# board.net
KiCad netlist of a schematic drawn in EAGLE
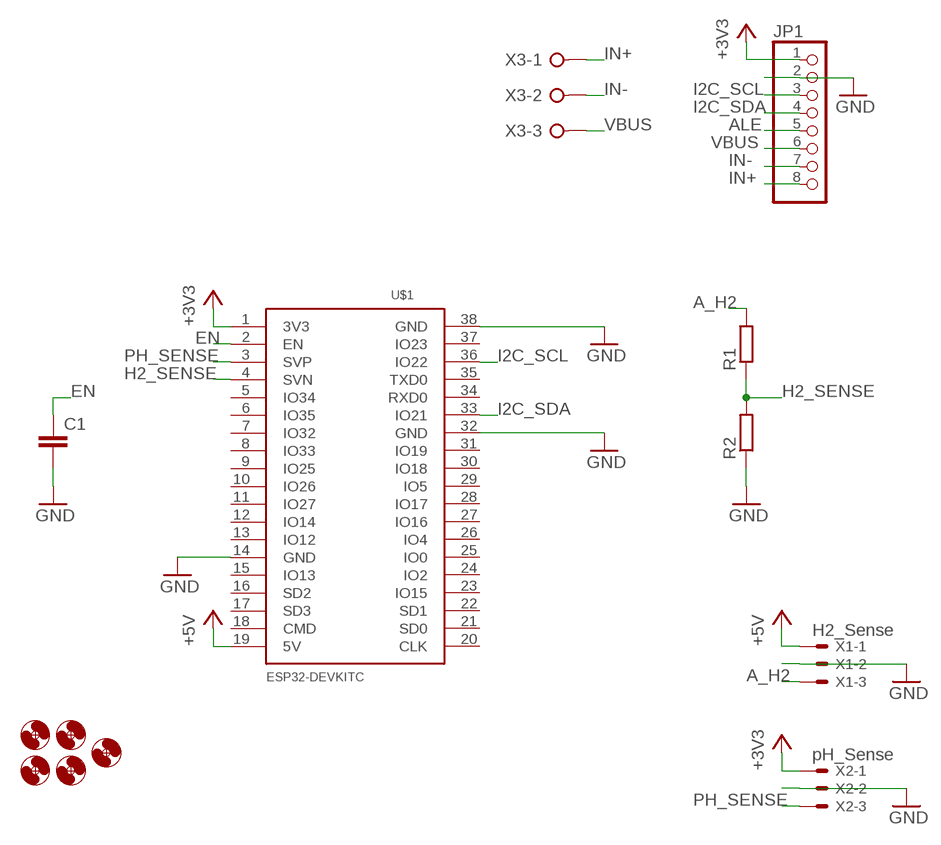
[diagram p0: schematic, sheet 1]

(export (version "E")
  (design (tool "Eeschema 10.0.6"))
  (components
    (comp (ref "C1")
      (value "C-EUC0805")
      (footprint "eagle-import:C0805")
      (libsource (lib "eagle-import") (part "C-EUC0805"))
    )
    (comp (ref "H1")
      (value "MOUNT-HOLE3.0")
      (footprint "eagle-import:3,0")
      (libsource (lib "eagle-import") (part "MOUNT-HOLE3.0"))
    )
    (comp (ref "H2")
      (value "MOUNT-HOLE3.0")
      (footprint "eagle-import:3,0")
      (libsource (lib "eagle-import") (part "MOUNT-HOLE3.0"))
    )
    (comp (ref "H3")
      (value "MOUNT-HOLE3.0")
      (footprint "eagle-import:3,0")
      (libsource (lib "eagle-import") (part "MOUNT-HOLE3.0"))
    )
    (comp (ref "H4")
      (value "MOUNT-HOLE3.0")
      (footprint "eagle-import:3,0")
      (libsource (lib "eagle-import") (part "MOUNT-HOLE3.0"))
    )
    (comp (ref "H6")
      (value "MOUNT-HOLE3.0")
      (footprint "eagle-import:3,0")
      (libsource (lib "eagle-import") (part "MOUNT-HOLE3.0"))
    )
    (comp (ref "JP1")
      (value "PINHD-1X8")
      (footprint "eagle-import:1X08")
      (libsource (lib "eagle-import") (part "PINHD-1X8"))
    )
    (comp (ref "R1")
      (value "R-EU_R0805")
      (footprint "eagle-import:R0805")
      (libsource (lib "eagle-import") (part "R-EU_R0805"))
    )
    (comp (ref "R2")
      (value "R-EU_R0805")
      (footprint "eagle-import:R0805")
      (libsource (lib "eagle-import") (part "R-EU_R0805"))
    )
    (comp (ref "U$1")
      (value "ESP32DEVKITC")
      (footprint "eagle-import:ESP32-DEVKITC")
      (libsource (lib "eagle-import") (part "ESP32DEVKITC"))
    )
    (comp (ref "X1")
      (value "H2_Sense")
      (footprint "eagle-import:JST-XH-03-PACKAGE-LONG-PAD")
      (libsource (lib "eagle-import") (part "JST-XH-03-PIN-LONG-PAD"))
    )
    (comp (ref "X2")
      (value "pH_Sense")
      (footprint "eagle-import:JST-XH-03-PACKAGE-LONG-PAD")
      (libsource (lib "eagle-import") (part "JST-XH-03-PIN-LONG-PAD"))
    )
    (comp (ref "X3")
      (value "W237-3E")
      (footprint "eagle-import:W237-3E")
      (libsource (lib "eagle-import") (part "W237-3E"))
    )
  )
  (nets
    (net (code "1") (name "+3V3") (class "Default")
      (node (ref "JP1") (pin "1") (pinfunction "1_1") (pintype "passive"))
      (node (ref "U$1") (pin "1") (pinfunction "3V3_1") (pintype "bidirectional"))
      (node (ref "X2") (pin "1") (pinfunction "S_1") (pintype "passive"))
    )
    (net (code "2") (name "+5V") (class "Default")
      (node (ref "U$1") (pin "19") (pinfunction "5V_19") (pintype "bidirectional"))
      (node (ref "X1") (pin "1") (pinfunction "S_1") (pintype "passive"))
    )
    (net (code "3") (name "/ALE") (class "Default")
      (node (ref "JP1") (pin "5") (pinfunction "5_5") (pintype "passive"))
    )
    (net (code "4") (name "/A_H2") (class "Default")
      (node (ref "R1") (pin "2") (pinfunction "2_2") (pintype "passive"))
      (node (ref "X1") (pin "3") (pinfunction "S_3") (pintype "passive"))
    )
    (net (code "5") (name "/EN") (class "Default")
      (node (ref "C1") (pin "1") (pinfunction "1_1") (pintype "passive"))
      (node (ref "U$1") (pin "2") (pinfunction "EN_2") (pintype "bidirectional"))
    )
    (net (code "6") (name "/H2_SENSE") (class "Default")
      (node (ref "R1") (pin "1") (pinfunction "1_1") (pintype "passive"))
      (node (ref "R2") (pin "2") (pinfunction "2_2") (pintype "passive"))
      (node (ref "U$1") (pin "4") (pinfunction "SVN_4") (pintype "bidirectional"))
    )
    (net (code "7") (name "/I2C_SCL") (class "Default")
      (node (ref "JP1") (pin "3") (pinfunction "3_3") (pintype "passive"))
      (node (ref "U$1") (pin "36") (pinfunction "IO22_36") (pintype "bidirectional"))
    )
    (net (code "8") (name "/I2C_SDA") (class "Default")
      (node (ref "JP1") (pin "4") (pinfunction "4_4") (pintype "passive"))
      (node (ref "U$1") (pin "33") (pinfunction "IO21_33") (pintype "bidirectional"))
    )
    (net (code "9") (name "/IN+") (class "Default")
      (node (ref "JP1") (pin "8") (pinfunction "8_8") (pintype "passive"))
      (node (ref "X3") (pin "1") (pinfunction "KL_1") (pintype "passive"))
    )
    (net (code "10") (name "/IN-") (class "Default")
      (node (ref "JP1") (pin "7") (pinfunction "7_7") (pintype "passive"))
      (node (ref "X3") (pin "2") (pinfunction "KL_2") (pintype "passive"))
    )
    (net (code "11") (name "/PH_SENSE") (class "Default")
      (node (ref "U$1") (pin "3") (pinfunction "SVP_3") (pintype "bidirectional"))
      (node (ref "X2") (pin "3") (pinfunction "S_3") (pintype "passive"))
    )
    (net (code "12") (name "/VBUS") (class "Default")
      (node (ref "JP1") (pin "6") (pinfunction "6_6") (pintype "passive"))
      (node (ref "X3") (pin "3") (pinfunction "KL_3") (pintype "passive"))
    )
    (net (code "13") (name "GND") (class "Default")
      (node (ref "C1") (pin "2") (pinfunction "2_2") (pintype "passive"))
      (node (ref "JP1") (pin "2") (pinfunction "2_2") (pintype "passive"))
      (node (ref "R2") (pin "1") (pinfunction "1_1") (pintype "passive"))
      (node (ref "U$1") (pin "14") (pinfunction "GND_14") (pintype "bidirectional"))
      (node (ref "U$1") (pin "32") (pinfunction "GND_32") (pintype "bidirectional"))
      (node (ref "U$1") (pin "38") (pinfunction "GND_38") (pintype "bidirectional"))
      (node (ref "X1") (pin "2") (pinfunction "S_2") (pintype "passive"))
      (node (ref "X2") (pin "2") (pinfunction "S_2") (pintype "passive"))
    )
    (net (code "14") (name "unconnected-(U$1-CLK-Pad20)") (class "Default")
      (node (ref "U$1") (pin "20") (pinfunction "CLK_20") (pintype "bidirectional"))
    )
    (net (code "15") (name "unconnected-(U$1-CMD-Pad18)") (class "Default")
      (node (ref "U$1") (pin "18") (pinfunction "CMD_18") (pintype "bidirectional"))
    )
    (net (code "16") (name "unconnected-(U$1-IO0-Pad25)") (class "Default")
      (node (ref "U$1") (pin "25") (pinfunction "IO0_25") (pintype "bidirectional"))
    )
    (net (code "17") (name "unconnected-(U$1-IO2-Pad24)") (class "Default")
      (node (ref "U$1") (pin "24") (pinfunction "IO2_24") (pintype "bidirectional"))
    )
    (net (code "18") (name "unconnected-(U$1-IO4-Pad26)") (class "Default")
      (node (ref "U$1") (pin "26") (pinfunction "IO4_26") (pintype "bidirectional"))
    )
    (net (code "19") (name "unconnected-(U$1-IO5-Pad29)") (class "Default")
      (node (ref "U$1") (pin "29") (pinfunction "IO5_29") (pintype "bidirectional"))
    )
    (net (code "20") (name "unconnected-(U$1-IO12-Pad13)") (class "Default")
      (node (ref "U$1") (pin "13") (pinfunction "IO12_13") (pintype "bidirectional"))
    )
    (net (code "21") (name "unconnected-(U$1-IO13-Pad15)") (class "Default")
      (node (ref "U$1") (pin "15") (pinfunction "IO13_15") (pintype "bidirectional"))
    )
    (net (code "22") (name "unconnected-(U$1-IO14-Pad12)") (class "Default")
      (node (ref "U$1") (pin "12") (pinfunction "IO14_12") (pintype "bidirectional"))
    )
    (net (code "23") (name "unconnected-(U$1-IO15-Pad23)") (class "Default")
      (node (ref "U$1") (pin "23") (pinfunction "IO15_23") (pintype "bidirectional"))
    )
    (net (code "24") (name "unconnected-(U$1-IO16-Pad27)") (class "Default")
      (node (ref "U$1") (pin "27") (pinfunction "IO16_27") (pintype "bidirectional"))
    )
    (net (code "25") (name "unconnected-(U$1-IO17-Pad28)") (class "Default")
      (node (ref "U$1") (pin "28") (pinfunction "IO17_28") (pintype "bidirectional"))
    )
    (net (code "26") (name "unconnected-(U$1-IO18-Pad30)") (class "Default")
      (node (ref "U$1") (pin "30") (pinfunction "IO18_30") (pintype "bidirectional"))
    )
    (net (code "27") (name "unconnected-(U$1-IO19-Pad31)") (class "Default")
      (node (ref "U$1") (pin "31") (pinfunction "IO19_31") (pintype "bidirectional"))
    )
    (net (code "28") (name "unconnected-(U$1-IO23-Pad37)") (class "Default")
      (node (ref "U$1") (pin "37") (pinfunction "IO23_37") (pintype "bidirectional"))
    )
    (net (code "29") (name "unconnected-(U$1-IO25-Pad9)") (class "Default")
      (node (ref "U$1") (pin "9") (pinfunction "IO25_9") (pintype "bidirectional"))
    )
    (net (code "30") (name "unconnected-(U$1-IO26-Pad10)") (class "Default")
      (node (ref "U$1") (pin "10") (pinfunction "IO26_10") (pintype "bidirectional"))
    )
    (net (code "31") (name "unconnected-(U$1-IO27-Pad11)") (class "Default")
      (node (ref "U$1") (pin "11") (pinfunction "IO27_11") (pintype "bidirectional"))
    )
    (net (code "32") (name "unconnected-(U$1-IO32-Pad7)") (class "Default")
      (node (ref "U$1") (pin "7") (pinfunction "IO32_7") (pintype "bidirectional"))
    )
    (net (code "33") (name "unconnected-(U$1-IO33-Pad8)") (class "Default")
      (node (ref "U$1") (pin "8") (pinfunction "IO33_8") (pintype "bidirectional"))
    )
    (net (code "34") (name "unconnected-(U$1-IO34-Pad5)") (class "Default")
      (node (ref "U$1") (pin "5") (pinfunction "IO34_5") (pintype "bidirectional"))
    )
    (net (code "35") (name "unconnected-(U$1-IO35-Pad6)") (class "Default")
      (node (ref "U$1") (pin "6") (pinfunction "IO35_6") (pintype "bidirectional"))
    )
    (net (code "36") (name "unconnected-(U$1-RXD0-Pad34)") (class "Default")
      (node (ref "U$1") (pin "34") (pinfunction "RXD0_34") (pintype "bidirectional"))
    )
    (net (code "37") (name "unconnected-(U$1-SD0-Pad21)") (class "Default")
      (node (ref "U$1") (pin "21") (pinfunction "SD0_21") (pintype "bidirectional"))
    )
    (net (code "38") (name "unconnected-(U$1-SD1-Pad22)") (class "Default")
      (node (ref "U$1") (pin "22") (pinfunction "SD1_22") (pintype "bidirectional"))
    )
    (net (code "39") (name "unconnected-(U$1-SD2-Pad16)") (class "Default")
      (node (ref "U$1") (pin "16") (pinfunction "SD2_16") (pintype "bidirectional"))
    )
    (net (code "40") (name "unconnected-(U$1-SD3-Pad17)") (class "Default")
      (node (ref "U$1") (pin "17") (pinfunction "SD3_17") (pintype "bidirectional"))
    )
    (net (code "41") (name "unconnected-(U$1-TXD0-Pad35)") (class "Default")
      (node (ref "U$1") (pin "35") (pinfunction "TXD0_35") (pintype "bidirectional"))
    )
  )
)
